# GPS-SD.net
KiCad netlist of a schematic drawn in Altium Designer
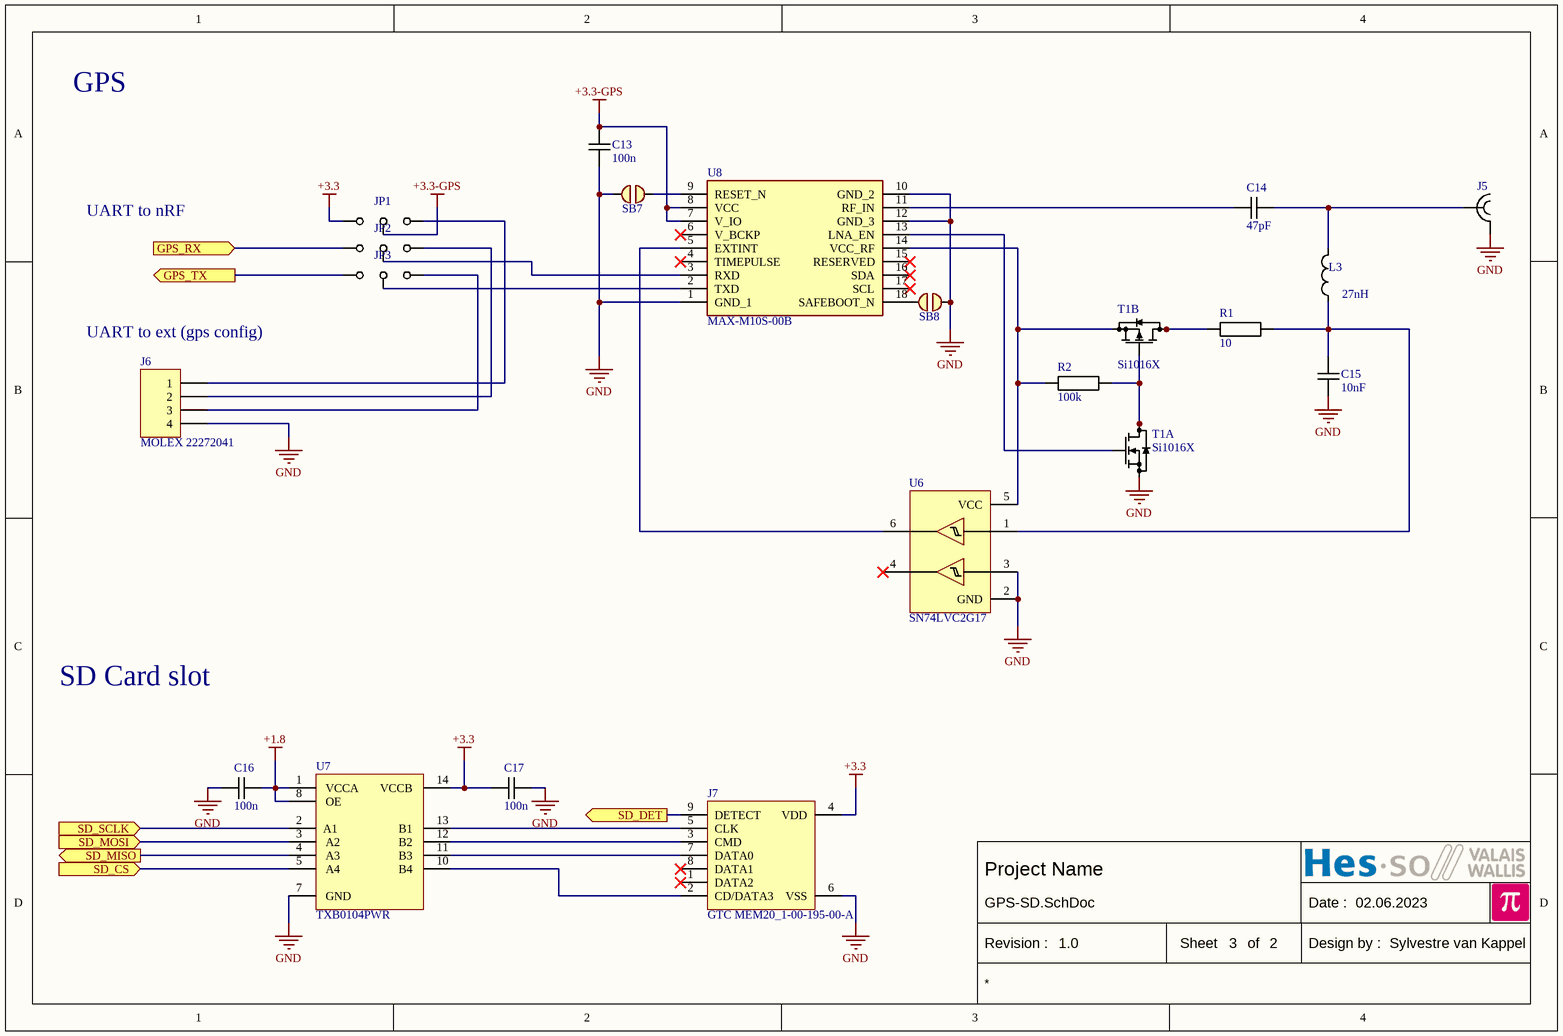
[diagram p0: GPS-SD.SchDoc]

(export (version "E")
  (design (tool "Eeschema 10.0.6"))
  (components
    (comp (ref "C13")
      (value "100n")
      (footprint "CAPACITOR 1608 REFLOW")
      (description "Capacitor")
      (libsource (lib "Capacitor") (part "Capacitor"))
    )
    (comp (ref "C14")
      (value "47pF")
      (footprint "CAPACITOR 1608 REFLOW")
      (description "Capacitor")
      (libsource (lib "Capacitor") (part "Capacitor"))
    )
    (comp (ref "C15")
      (value "10nF")
      (footprint "CAPACITOR 1608 REFLOW")
      (description "Capacitor")
      (libsource (lib "Capacitor") (part "Capacitor"))
    )
    (comp (ref "C16")
      (value "100n")
      (footprint "CAPACITOR 1608 REFLOW")
      (description "Capacitor")
      (libsource (lib "Capacitor") (part "Capacitor"))
    )
    (comp (ref "C17")
      (value "100n")
      (footprint "CAPACITOR 1608 REFLOW")
      (description "Capacitor")
      (libsource (lib "Capacitor") (part "Capacitor"))
    )
    (comp (ref "J5")
      (value "732511150")
      (footprint "SMA EDGE Molex 732511150")
      (description "SMA EDGE Molex 732511150")
      (libsource (lib "Connector") (part "SMA EDGE Molex 732511150"))
    )
    (comp (ref "J6")
      (value "MOLEX 22272041")
      (footprint "MOLEX 22272041")
      (description "KK 254 Wire-to-Board Header, Vertical, 4 Circuits")
      (libsource (lib "Connector") (part "MOLEX 22272041"))
    )
    (comp (ref "J7")
      (value "GTC MEM20_1-00-195-00-A")
      (footprint "SD MICRO GCT MEM2051-00-195-00-A")
      (description "SD Card Micro")
      (fields (field (name "MF") "Global Connector Technology") (field (name "MP") "MEM2051-00-195-00-A"))
      (libsource (lib "Connector") (part "SD-MICRO GTC MEM20_1-00-195-00-A"))
    )
    (comp (ref "JP1")
      (value "{Value}")
      (footprint "JUMPER3 SMD 1608")
      (description "JUMPER 3 POS")
      (libsource (lib "Jumper") (part "JUMPER 3 POS"))
    )
    (comp (ref "JP2")
      (value "{Value}")
      (footprint "JUMPER3 SMD 1608")
      (description "JUMPER 3 POS")
      (libsource (lib "Jumper") (part "JUMPER 3 POS"))
    )
    (comp (ref "JP3")
      (value "{Value}")
      (footprint "JUMPER3 SMD 1608")
      (description "JUMPER 3 POS")
      (libsource (lib "Jumper") (part "JUMPER 3 POS"))
    )
    (comp (ref "L3")
      (value "27nH")
      (footprint "INDUCTOR 1608 REFLOW")
      (description "Inductor")
      (libsource (lib "Inductor") (part "Inductor"))
    )
    (comp (ref "R1")
      (value "10")
      (footprint "RESISTOR 1608 REFLOW")
      (description "Resistor")
      (libsource (lib "Resistor") (part "Resistor"))
    )
    (comp (ref "R2")
      (value "100k")
      (footprint "RESISTOR 1608 REFLOW")
      (description "Resistor")
      (libsource (lib "Resistor") (part "Resistor"))
    )
    (comp (ref "SB7")
      (value "*")
      (footprint "Solder Bridge 1mm Unconnected")
      (description "Solderbridge Unconnected")
      (libsource (lib "Jumper") (part "Solderbridge Unconnected"))
    )
    (comp (ref "SB8")
      (value "*")
      (footprint "Solder Bridge 1mm Unconnected")
      (description "Solderbridge Unconnected")
      (libsource (lib "Jumper") (part "Solderbridge Unconnected"))
    )
    (comp (ref "T1")
      (value "Si1016X")
      (footprint "SOT563F P0.5 C1.6x1.2 H0.6")
      (description "Complementary N- and P-Channel 20 V (D-S) MOSFET")
      (libsource (lib "Transistor") (part "Si1016X"))
    )
    (comp (ref "U6")
      (value "SN74LVC2G17")
      (footprint "SOT23-6 P0.95 C1.5x3.0 H1.3")
      (description "Dual Schmitt-Trigger Buffer")
      (libsource (lib "IntegratedCircuit") (part "SN74LVC2G17"))
    )
    (comp (ref "U7")
      (value "TXB0104PWR")
      (footprint "TSSOP14 P0.65 C4.4x5.0 H1.1")
      (libsource (lib "IntegratedCircuit") (part "TXB0104PWR"))
    )
    (comp (ref "U8")
      (value "MAX-M10S-00B")
      (footprint "MAXM10S00B")
      (description "Standard precision GNSS module")
      (libsource (lib "WirelessDevice") (part "MAX-M10S-00B"))
    )
  )
  (nets
    (net (code "1") (name "+1.8") (class "Default")
      (node (ref "C16") (pin "2") (pinfunction "2_2") (pintype "passive"))
      (node (ref "U7") (pin "1") (pinfunction "VCCA_1") (pintype "passive"))
      (node (ref "U7") (pin "8") (pinfunction "OE_8") (pintype "passive"))
    )
    (net (code "2") (name "+3.3") (class "Default")
      (node (ref "C17") (pin "2") (pinfunction "2_2") (pintype "passive"))
      (node (ref "J7") (pin "4") (pinfunction "VDD_4") (pintype "power_in"))
      (node (ref "JP1") (pin "1") (pinfunction "1_1") (pintype "passive"))
      (node (ref "U7") (pin "14") (pinfunction "VCCB_14") (pintype "passive"))
    )
    (net (code "3") (name "+3.3-GPS") (class "Default")
      (node (ref "C13") (pin "1") (pinfunction "1_1") (pintype "passive"))
      (node (ref "JP1") (pin "2") (pinfunction "2_2") (pintype "passive"))
      (node (ref "U8") (pin "7") (pinfunction "V_IO_7") (pintype "passive"))
      (node (ref "U8") (pin "8") (pinfunction "VCC_8") (pintype "passive"))
    )
    (net (code "4") (name "/GPS_RX") (class "Default")
      (node (ref "JP2") (pin "1") (pinfunction "1_1") (pintype "passive"))
    )
    (net (code "5") (name "/GPS_TX") (class "Default")
      (node (ref "JP3") (pin "1") (pinfunction "1_1") (pintype "passive"))
    )
    (net (code "6") (name "/SD_CS") (class "Default")
      (node (ref "U7") (pin "5") (pinfunction "A4_5") (pintype "passive"))
    )
    (net (code "7") (name "/SD_DET") (class "Default")
      (node (ref "J7") (pin "9") (pinfunction "DETECT_9") (pintype "passive"))
    )
    (net (code "8") (name "/SD_MISO") (class "Default")
      (node (ref "U7") (pin "4") (pinfunction "A3_4") (pintype "passive"))
    )
    (net (code "9") (name "/SD_MOSI") (class "Default")
      (node (ref "U7") (pin "3") (pinfunction "A2_3") (pintype "passive"))
    )
    (net (code "10") (name "/SD_SCLK") (class "Default")
      (node (ref "U7") (pin "2") (pinfunction "A1_2") (pintype "passive"))
    )
    (net (code "11") (name "GND") (class "Default")
      (node (ref "C13") (pin "2") (pinfunction "2_2") (pintype "passive"))
      (node (ref "C15") (pin "1") (pinfunction "1_1") (pintype "passive"))
      (node (ref "C16") (pin "1") (pinfunction "1_1") (pintype "passive"))
      (node (ref "C17") (pin "1") (pinfunction "1_1") (pintype "passive"))
      (node (ref "J5") (pin "2") (pinfunction "2_2") (pintype "passive"))
      (node (ref "J6") (pin "4") (pinfunction "4_4") (pintype "passive"))
      (node (ref "J7") (pin "6") (pinfunction "VSS_6") (pintype "power_in"))
      (node (ref "SB7") (pin "1") (pinfunction "0_1") (pintype "passive"))
      (node (ref "SB8") (pin "2") (pinfunction "1_2") (pintype "passive"))
      (node (ref "T1") (pin "1") (pinfunction "S1_1") (pintype "passive"))
      (node (ref "U6") (pin "2") (pinfunction "GND_2") (pintype "passive"))
      (node (ref "U6") (pin "3") (pinfunction "2A_3") (pintype "passive"))
      (node (ref "U7") (pin "7") (pinfunction "GND_7") (pintype "passive"))
      (node (ref "U8") (pin "1") (pinfunction "GND_1_1") (pintype "passive"))
      (node (ref "U8") (pin "10") (pinfunction "GND_2_10") (pintype "passive"))
      (node (ref "U8") (pin "12") (pinfunction "GND_3_12") (pintype "passive"))
    )
    (net (code "12") (name "Net-(C14-Pad1)") (class "Default")
      (node (ref "C14") (pin "1") (pinfunction "1_1") (pintype "passive"))
      (node (ref "J5") (pin "1") (pinfunction "1_1") (pintype "passive"))
      (node (ref "L3") (pin "2") (pinfunction "2_2") (pintype "passive"))
    )
    (net (code "13") (name "Net-(J6-Pad1)") (class "Default")
      (node (ref "J6") (pin "1") (pinfunction "1_1") (pintype "passive"))
      (node (ref "JP1") (pin "3") (pinfunction "3_3") (pintype "passive"))
    )
    (net (code "14") (name "Net-(J6-Pad2)") (class "Default")
      (node (ref "J6") (pin "2") (pinfunction "2_2") (pintype "passive"))
      (node (ref "JP2") (pin "3") (pinfunction "3_3") (pintype "passive"))
    )
    (net (code "15") (name "Net-(J6-Pad3)") (class "Default")
      (node (ref "J6") (pin "3") (pinfunction "3_3") (pintype "passive"))
      (node (ref "JP3") (pin "3") (pinfunction "3_3") (pintype "passive"))
    )
    (net (code "16") (name "Net-(J7-CD{slash}DATA3)") (class "Default")
      (node (ref "J7") (pin "2") (pinfunction "CD/DATA3_2") (pintype "passive"))
      (node (ref "U7") (pin "10") (pinfunction "B4_10") (pintype "passive"))
    )
    (net (code "17") (name "Net-(J7-CLK)") (class "Default")
      (node (ref "J7") (pin "5") (pinfunction "CLK_5") (pintype "passive"))
      (node (ref "U7") (pin "13") (pinfunction "B1_13") (pintype "passive"))
    )
    (net (code "18") (name "Net-(J7-CMD)") (class "Default")
      (node (ref "J7") (pin "3") (pinfunction "CMD_3") (pintype "passive"))
      (node (ref "U7") (pin "12") (pinfunction "B2_12") (pintype "passive"))
    )
    (net (code "19") (name "Net-(J7-DATA0)") (class "Default")
      (node (ref "J7") (pin "7") (pinfunction "DATA0_7") (pintype "passive"))
      (node (ref "U7") (pin "11") (pinfunction "B3_11") (pintype "passive"))
    )
    (net (code "20") (name "Net-(R1-Pad1)") (class "Default")
      (node (ref "R1") (pin "1") (pinfunction "1_1") (pintype "passive"))
      (node (ref "T1") (pin "3") (pinfunction "D2_3") (pintype "passive"))
      (node (ref "T1") (pin "5") (pinfunction "D2_5") (pintype "passive"))
    )
    (net (code "21") (name "Net-(SB7-1)") (class "Default")
      (node (ref "SB7") (pin "2") (pinfunction "1_2") (pintype "passive"))
      (node (ref "U8") (pin "9") (pinfunction "RESET_N_9") (pintype "passive"))
    )
    (net (code "22") (name "Net-(SB8-0)") (class "Default")
      (node (ref "SB8") (pin "1") (pinfunction "0_1") (pintype "passive"))
      (node (ref "U8") (pin "18") (pinfunction "SAFEBOOT_N_18") (pintype "passive"))
    )
    (net (code "23") (name "Net-(T1A-G1)") (class "Default")
      (node (ref "T1") (pin "2") (pinfunction "G1_2") (pintype "passive"))
      (node (ref "U8") (pin "13") (pinfunction "LNA_EN_13") (pintype "passive"))
    )
    (net (code "24") (name "Net-(T1B-G2)") (class "Default")
      (node (ref "R2") (pin "2") (pinfunction "2_2") (pintype "passive"))
      (node (ref "T1") (pin "5") (pinfunction "G2_5") (pintype "passive"))
      (node (ref "T1") (pin "6") (pinfunction "D1_6") (pintype "passive"))
      (node (ref "T1") (pin "7") (pinfunction "D1_7") (pintype "passive"))
    )
    (net (code "25") (name "Net-(T1B-S2)") (class "Default")
      (node (ref "R2") (pin "1") (pinfunction "1_1") (pintype "passive"))
      (node (ref "T1") (pin "4") (pinfunction "S2_4") (pintype "passive"))
      (node (ref "U6") (pin "5") (pinfunction "VCC_5") (pintype "passive"))
      (node (ref "U8") (pin "14") (pinfunction "VCC_RF_14") (pintype "passive"))
    )
    (net (code "26") (name "Net-(U6-1A)") (class "Default")
      (node (ref "C15") (pin "2") (pinfunction "2_2") (pintype "passive"))
      (node (ref "L3") (pin "1") (pinfunction "1_1") (pintype "passive"))
      (node (ref "R1") (pin "2") (pinfunction "2_2") (pintype "passive"))
      (node (ref "U6") (pin "1") (pinfunction "1A_1") (pintype "passive"))
    )
    (net (code "27") (name "Net-(U6-1Y)") (class "Default")
      (node (ref "U6") (pin "6") (pinfunction "1Y_6") (pintype "passive"))
      (node (ref "U8") (pin "5") (pinfunction "EXTINT_5") (pintype "passive"))
    )
    (net (code "28") (name "Net-(U8-RF_IN)") (class "Default")
      (node (ref "C14") (pin "2") (pinfunction "2_2") (pintype "passive"))
      (node (ref "U8") (pin "11") (pinfunction "RF_IN_11") (pintype "passive"))
    )
    (net (code "29") (name "Net-(U8-RXD)") (class "Default")
      (node (ref "JP2") (pin "2") (pinfunction "2_2") (pintype "passive"))
      (node (ref "U8") (pin "3") (pinfunction "RXD_3") (pintype "passive"))
    )
    (net (code "30") (name "Net-(U8-TXD)") (class "Default")
      (node (ref "JP3") (pin "2") (pinfunction "2_2") (pintype "passive"))
      (node (ref "U8") (pin "2") (pinfunction "TXD_2") (pintype "passive"))
    )
    (net (code "31") (name "unconnected-(J7-DATA1-Pad8)") (class "Default")
      (node (ref "J7") (pin "8") (pinfunction "DATA1_8") (pintype "passive+no_connect"))
    )
    (net (code "32") (name "unconnected-(J7-DATA2-Pad1)") (class "Default")
      (node (ref "J7") (pin "1") (pinfunction "DATA2_1") (pintype "passive+no_connect"))
    )
    (net (code "33") (name "unconnected-(U6-2Y-Pad4)") (class "Default")
      (node (ref "U6") (pin "4") (pinfunction "2Y_4") (pintype "passive+no_connect"))
    )
    (net (code "34") (name "unconnected-(U8-RESERVED-Pad15)") (class "Default")
      (node (ref "U8") (pin "15") (pinfunction "RESERVED_15") (pintype "passive+no_connect"))
    )
    (net (code "35") (name "unconnected-(U8-SCL-Pad17)") (class "Default")
      (node (ref "U8") (pin "17") (pinfunction "SCL_17") (pintype "passive+no_connect"))
    )
    (net (code "36") (name "unconnected-(U8-SDA-Pad16)") (class "Default")
      (node (ref "U8") (pin "16") (pinfunction "SDA_16") (pintype "passive+no_connect"))
    )
    (net (code "37") (name "unconnected-(U8-TIMEPULSE-Pad4)") (class "Default")
      (node (ref "U8") (pin "4") (pinfunction "TIMEPULSE_4") (pintype "passive+no_connect"))
    )
    (net (code "38") (name "unconnected-(U8-V_BCKP-Pad6)") (class "Default")
      (node (ref "U8") (pin "6") (pinfunction "V_BCKP_6") (pintype "passive+no_connect"))
    )
  )
)
